# tank_control.net
KiCad netlist of a schematic drawn in Altium Designer
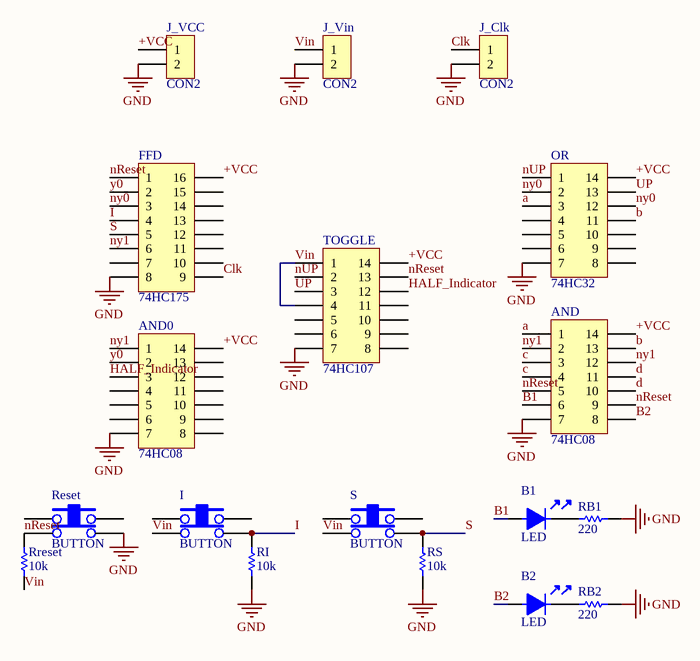
[diagram p0: tank_control.SchDoc]

(export (version "E")
  (design (tool "Eeschema 10.0.6"))
  (components
    (comp (ref "AND") (value "74HC08") (footprint "DIP14") (libsource (lib "LIBEBAL") (part "IC_DIP14")))
    (comp (ref "AND0") (value "74HC08") (footprint "DIP14") (libsource (lib "LIBEBAL") (part "IC_DIP14")))
    (comp (ref "B1") (value "LED") (footprint "LED3") (libsource (lib "LIBEBAL") (part "LED")))
    (comp (ref "B2") (value "LED") (footprint "LED3") (libsource (lib "LIBEBAL") (part "LED")))
    (comp (ref "FFD") (value "74HC175") (footprint "DIP16") (libsource (lib "LIBEBAL") (part "IC_DIP16")))
    (comp (ref "I")
      (value "BUTTON")
      (footprint "TACTSWITCH")
      (libsource (lib "LIBEBAL") (part "TACT SWITCH"))
    )
    (comp (ref "J_Clk") (value "CON2") (footprint "SIP2") (libsource (lib "LIBEBAL") (part "CON2")))
    (comp (ref "J_VCC") (value "CON2") (footprint "SIP2") (libsource (lib "LIBEBAL") (part "CON2")))
    (comp (ref "J_Vin") (value "CON2") (footprint "SIP2") (libsource (lib "LIBEBAL") (part "CON2")))
    (comp (ref "OR") (value "74HC32") (footprint "DIP14") (libsource (lib "LIBEBAL") (part "IC_DIP14")))
    (comp (ref "RB1") (value "220") (footprint "RES400") (libsource (lib "LIBEBAL") (part "RES")))
    (comp (ref "RB2") (value "220") (footprint "RES400") (libsource (lib "LIBEBAL") (part "RES")))
    (comp (ref "Reset")
      (value "BUTTON")
      (footprint "TACTSWITCH")
      (libsource (lib "LIBEBAL") (part "TACT SWITCH"))
    )
    (comp (ref "RI") (value "10k") (footprint "RES400") (libsource (lib "LIBEBAL") (part "RES")))
    (comp (ref "Rreset") (value "10k") (footprint "RES400") (libsource (lib "LIBEBAL") (part "RES")))
    (comp (ref "RS") (value "10k") (footprint "RES400") (libsource (lib "LIBEBAL") (part "RES")))
    (comp (ref "S")
      (value "BUTTON")
      (footprint "TACTSWITCH")
      (libsource (lib "LIBEBAL") (part "TACT SWITCH"))
    )
    (comp (ref "TOGGLE") (value "74HC107") (footprint "DIP14") (libsource (lib "LIBEBAL") (part "IC_DIP14")))
  )
  (nets
    (net (code "1") (name "/+VCC") (class "Default")
      (node (ref "AND") (pin "14") (pinfunction "14_14") (pintype "passive"))
      (node (ref "AND0") (pin "14") (pinfunction "14_14") (pintype "passive"))
      (node (ref "FFD") (pin "16") (pinfunction "16_16") (pintype "passive"))
      (node (ref "J_VCC") (pin "1") (pinfunction "1_1") (pintype "passive"))
      (node (ref "OR") (pin "14") (pinfunction "14_14") (pintype "passive"))
      (node (ref "TOGGLE") (pin "14") (pinfunction "14_14") (pintype "passive"))
    )
    (net (code "2") (name "/B1") (class "Default")
      (node (ref "AND") (pin "6") (pinfunction "6_6") (pintype "passive"))
      (node (ref "B1") (pin "1") (pinfunction "1_1") (pintype "passive"))
    )
    (net (code "3") (name "/B2") (class "Default")
      (node (ref "AND") (pin "8") (pinfunction "8_8") (pintype "passive"))
      (node (ref "B2") (pin "1") (pinfunction "1_1") (pintype "passive"))
    )
    (net (code "4") (name "/Clk") (class "Default")
      (node (ref "FFD") (pin "9") (pinfunction "9_9") (pintype "passive"))
      (node (ref "J_Clk") (pin "1") (pinfunction "1_1") (pintype "passive"))
    )
    (net (code "5") (name "/HALF_Indicator") (class "Default")
      (node (ref "AND0") (pin "3") (pinfunction "3_3") (pintype "passive"))
      (node (ref "TOGGLE") (pin "12") (pinfunction "12_12") (pintype "passive"))
    )
    (net (code "6") (name "/I") (class "Default")
      (node (ref "FFD") (pin "4") (pinfunction "4_4") (pintype "passive"))
      (node (ref "I") (pin "4") (pinfunction "4_4") (pintype "passive"))
      (node (ref "RI") (pin "2") (pinfunction "2_2") (pintype "passive"))
    )
    (net (code "7") (name "/S") (class "Default")
      (node (ref "FFD") (pin "5") (pinfunction "5_5") (pintype "passive"))
      (node (ref "RS") (pin "2") (pinfunction "2_2") (pintype "passive"))
      (node (ref "S") (pin "4") (pinfunction "4_4") (pintype "passive"))
    )
    (net (code "8") (name "/UP") (class "Default")
      (node (ref "OR") (pin "13") (pinfunction "13_13") (pintype "passive"))
      (node (ref "TOGGLE") (pin "3") (pinfunction "3_3") (pintype "passive"))
    )
    (net (code "9") (name "/Vin") (class "Default")
      (node (ref "I") (pin "2") (pinfunction "2_2") (pintype "passive"))
      (node (ref "J_Vin") (pin "1") (pinfunction "1_1") (pintype "passive"))
      (node (ref "Rreset") (pin "1") (pinfunction "1_1") (pintype "passive"))
      (node (ref "S") (pin "2") (pinfunction "2_2") (pintype "passive"))
      (node (ref "TOGGLE") (pin "1") (pinfunction "1_1") (pintype "passive"))
      (node (ref "TOGGLE") (pin "4") (pinfunction "4_4") (pintype "passive"))
    )
    (net (code "10") (name "/a") (class "Default")
      (node (ref "AND") (pin "1") (pinfunction "1_1") (pintype "passive"))
      (node (ref "OR") (pin "3") (pinfunction "3_3") (pintype "passive"))
    )
    (net (code "11") (name "/b") (class "Default")
      (node (ref "AND") (pin "13") (pinfunction "13_13") (pintype "passive"))
      (node (ref "OR") (pin "11") (pinfunction "11_11") (pintype "passive"))
    )
    (net (code "12") (name "/c") (class "Default")
      (node (ref "AND") (pin "3") (pinfunction "3_3") (pintype "passive"))
      (node (ref "AND") (pin "4") (pinfunction "4_4") (pintype "passive"))
    )
    (net (code "13") (name "/d") (class "Default")
      (node (ref "AND") (pin "10") (pinfunction "10_10") (pintype "passive"))
      (node (ref "AND") (pin "11") (pinfunction "11_11") (pintype "passive"))
    )
    (net (code "14") (name "/nReset") (class "Default")
      (node (ref "AND") (pin "5") (pinfunction "5_5") (pintype "passive"))
      (node (ref "AND") (pin "9") (pinfunction "9_9") (pintype "passive"))
      (node (ref "FFD") (pin "1") (pinfunction "1_1") (pintype "passive"))
      (node (ref "Reset") (pin "2") (pinfunction "2_2") (pintype "passive"))
      (node (ref "Rreset") (pin "2") (pinfunction "2_2") (pintype "passive"))
      (node (ref "TOGGLE") (pin "13") (pinfunction "13_13") (pintype "passive"))
    )
    (net (code "15") (name "/nUP") (class "Default")
      (node (ref "OR") (pin "1") (pinfunction "1_1") (pintype "passive"))
      (node (ref "TOGGLE") (pin "2") (pinfunction "2_2") (pintype "passive"))
    )
    (net (code "16") (name "/ny0") (class "Default")
      (node (ref "FFD") (pin "3") (pinfunction "3_3") (pintype "passive"))
      (node (ref "OR") (pin "12") (pinfunction "12_12") (pintype "passive"))
      (node (ref "OR") (pin "2") (pinfunction "2_2") (pintype "passive"))
    )
    (net (code "17") (name "/ny1") (class "Default")
      (node (ref "AND") (pin "12") (pinfunction "12_12") (pintype "passive"))
      (node (ref "AND") (pin "2") (pinfunction "2_2") (pintype "passive"))
      (node (ref "AND0") (pin "1") (pinfunction "1_1") (pintype "passive"))
      (node (ref "FFD") (pin "6") (pinfunction "6_6") (pintype "passive"))
    )
    (net (code "18") (name "/y0") (class "Default")
      (node (ref "AND0") (pin "2") (pinfunction "2_2") (pintype "passive"))
      (node (ref "FFD") (pin "2") (pinfunction "2_2") (pintype "passive"))
    )
    (net (code "19") (name "GND") (class "Default")
      (node (ref "AND") (pin "7") (pinfunction "7_7") (pintype "passive"))
      (node (ref "AND0") (pin "7") (pinfunction "7_7") (pintype "passive"))
      (node (ref "FFD") (pin "8") (pinfunction "8_8") (pintype "passive"))
      (node (ref "J_Clk") (pin "2") (pinfunction "2_2") (pintype "passive"))
      (node (ref "J_VCC") (pin "2") (pinfunction "2_2") (pintype "passive"))
      (node (ref "J_Vin") (pin "2") (pinfunction "2_2") (pintype "passive"))
      (node (ref "OR") (pin "7") (pinfunction "7_7") (pintype "passive"))
      (node (ref "RB1") (pin "1") (pinfunction "1_1") (pintype "passive"))
      (node (ref "RB2") (pin "1") (pinfunction "1_1") (pintype "passive"))
      (node (ref "RI") (pin "1") (pinfunction "1_1") (pintype "passive"))
      (node (ref "RS") (pin "1") (pinfunction "1_1") (pintype "passive"))
      (node (ref "Reset") (pin "4") (pinfunction "4_4") (pintype "passive"))
      (node (ref "TOGGLE") (pin "7") (pinfunction "7_7") (pintype "passive"))
    )
    (net (code "20") (name "Net-(B1-Pad2)") (class "Default")
      (node (ref "B1") (pin "2") (pinfunction "2_2") (pintype "passive"))
      (node (ref "RB1") (pin "2") (pinfunction "2_2") (pintype "passive"))
    )
    (net (code "21") (name "Net-(B2-Pad2)") (class "Default")
      (node (ref "B2") (pin "2") (pinfunction "2_2") (pintype "passive"))
      (node (ref "RB2") (pin "2") (pinfunction "2_2") (pintype "passive"))
    )
    (net (code "22") (name "unconnected-(AND0-Pad4)") (class "Default")
      (node (ref "AND0") (pin "4") (pinfunction "4_4") (pintype "passive"))
    )
    (net (code "23") (name "unconnected-(AND0-Pad5)") (class "Default")
      (node (ref "AND0") (pin "5") (pinfunction "5_5") (pintype "passive"))
    )
    (net (code "24") (name "unconnected-(AND0-Pad6)") (class "Default")
      (node (ref "AND0") (pin "6") (pinfunction "6_6") (pintype "passive"))
    )
    (net (code "25") (name "unconnected-(AND0-Pad8)") (class "Default")
      (node (ref "AND0") (pin "8") (pinfunction "8_8") (pintype "passive"))
    )
    (net (code "26") (name "unconnected-(AND0-Pad9)") (class "Default")
      (node (ref "AND0") (pin "9") (pinfunction "9_9") (pintype "passive"))
    )
    (net (code "27") (name "unconnected-(AND0-Pad10)") (class "Default")
      (node (ref "AND0") (pin "10") (pinfunction "10_10") (pintype "passive"))
    )
    (net (code "28") (name "unconnected-(AND0-Pad11)") (class "Default")
      (node (ref "AND0") (pin "11") (pinfunction "11_11") (pintype "passive"))
    )
    (net (code "29") (name "unconnected-(AND0-Pad12)") (class "Default")
      (node (ref "AND0") (pin "12") (pinfunction "12_12") (pintype "passive"))
    )
    (net (code "30") (name "unconnected-(AND0-Pad13)") (class "Default")
      (node (ref "AND0") (pin "13") (pinfunction "13_13") (pintype "passive"))
    )
    (net (code "31") (name "unconnected-(FFD-Pad7)") (class "Default")
      (node (ref "FFD") (pin "7") (pinfunction "7_7") (pintype "passive"))
    )
    (net (code "32") (name "unconnected-(FFD-Pad10)") (class "Default")
      (node (ref "FFD") (pin "10") (pinfunction "10_10") (pintype "passive"))
    )
    (net (code "33") (name "unconnected-(FFD-Pad11)") (class "Default")
      (node (ref "FFD") (pin "11") (pinfunction "11_11") (pintype "passive"))
    )
    (net (code "34") (name "unconnected-(FFD-Pad12)") (class "Default")
      (node (ref "FFD") (pin "12") (pinfunction "12_12") (pintype "passive"))
    )
    (net (code "35") (name "unconnected-(FFD-Pad13)") (class "Default")
      (node (ref "FFD") (pin "13") (pinfunction "13_13") (pintype "passive"))
    )
    (net (code "36") (name "unconnected-(FFD-Pad14)") (class "Default")
      (node (ref "FFD") (pin "14") (pinfunction "14_14") (pintype "passive"))
    )
    (net (code "37") (name "unconnected-(FFD-Pad15)") (class "Default")
      (node (ref "FFD") (pin "15") (pinfunction "15_15") (pintype "passive"))
    )
    (net (code "38") (name "unconnected-(I-Pad1)") (class "Default")
      (node (ref "I") (pin "1") (pinfunction "1_1") (pintype "passive"))
    )
    (net (code "39") (name "unconnected-(I-Pad3)") (class "Default")
      (node (ref "I") (pin "3") (pinfunction "3_3") (pintype "passive"))
    )
    (net (code "40") (name "unconnected-(OR-Pad4)") (class "Default")
      (node (ref "OR") (pin "4") (pinfunction "4_4") (pintype "passive"))
    )
    (net (code "41") (name "unconnected-(OR-Pad5)") (class "Default")
      (node (ref "OR") (pin "5") (pinfunction "5_5") (pintype "passive"))
    )
    (net (code "42") (name "unconnected-(OR-Pad6)") (class "Default")
      (node (ref "OR") (pin "6") (pinfunction "6_6") (pintype "passive"))
    )
    (net (code "43") (name "unconnected-(OR-Pad8)") (class "Default")
      (node (ref "OR") (pin "8") (pinfunction "8_8") (pintype "passive"))
    )
    (net (code "44") (name "unconnected-(OR-Pad9)") (class "Default")
      (node (ref "OR") (pin "9") (pinfunction "9_9") (pintype "passive"))
    )
    (net (code "45") (name "unconnected-(OR-Pad10)") (class "Default")
      (node (ref "OR") (pin "10") (pinfunction "10_10") (pintype "passive"))
    )
    (net (code "46") (name "unconnected-(Reset-Pad1)") (class "Default")
      (node (ref "Reset") (pin "1") (pinfunction "1_1") (pintype "passive"))
    )
    (net (code "47") (name "unconnected-(Reset-Pad3)") (class "Default")
      (node (ref "Reset") (pin "3") (pinfunction "3_3") (pintype "passive"))
    )
    (net (code "48") (name "unconnected-(S-Pad1)") (class "Default")
      (node (ref "S") (pin "1") (pinfunction "1_1") (pintype "passive"))
    )
    (net (code "49") (name "unconnected-(S-Pad3)") (class "Default")
      (node (ref "S") (pin "3") (pinfunction "3_3") (pintype "passive"))
    )
    (net (code "50") (name "unconnected-(TOGGLE-Pad5)") (class "Default")
      (node (ref "TOGGLE") (pin "5") (pinfunction "5_5") (pintype "passive"))
    )
    (net (code "51") (name "unconnected-(TOGGLE-Pad6)") (class "Default")
      (node (ref "TOGGLE") (pin "6") (pinfunction "6_6") (pintype "passive"))
    )
    (net (code "52") (name "unconnected-(TOGGLE-Pad8)") (class "Default")
      (node (ref "TOGGLE") (pin "8") (pinfunction "8_8") (pintype "passive"))
    )
    (net (code "53") (name "unconnected-(TOGGLE-Pad9)") (class "Default")
      (node (ref "TOGGLE") (pin "9") (pinfunction "9_9") (pintype "passive"))
    )
    (net (code "54") (name "unconnected-(TOGGLE-Pad10)") (class "Default")
      (node (ref "TOGGLE") (pin "10") (pinfunction "10_10") (pintype "passive"))
    )
    (net (code "55") (name "unconnected-(TOGGLE-Pad11)") (class "Default")
      (node (ref "TOGGLE") (pin "11") (pinfunction "11_11") (pintype "passive"))
    )
  )
)
